# MCU.net
KiCad netlist of a schematic drawn in Altium Designer
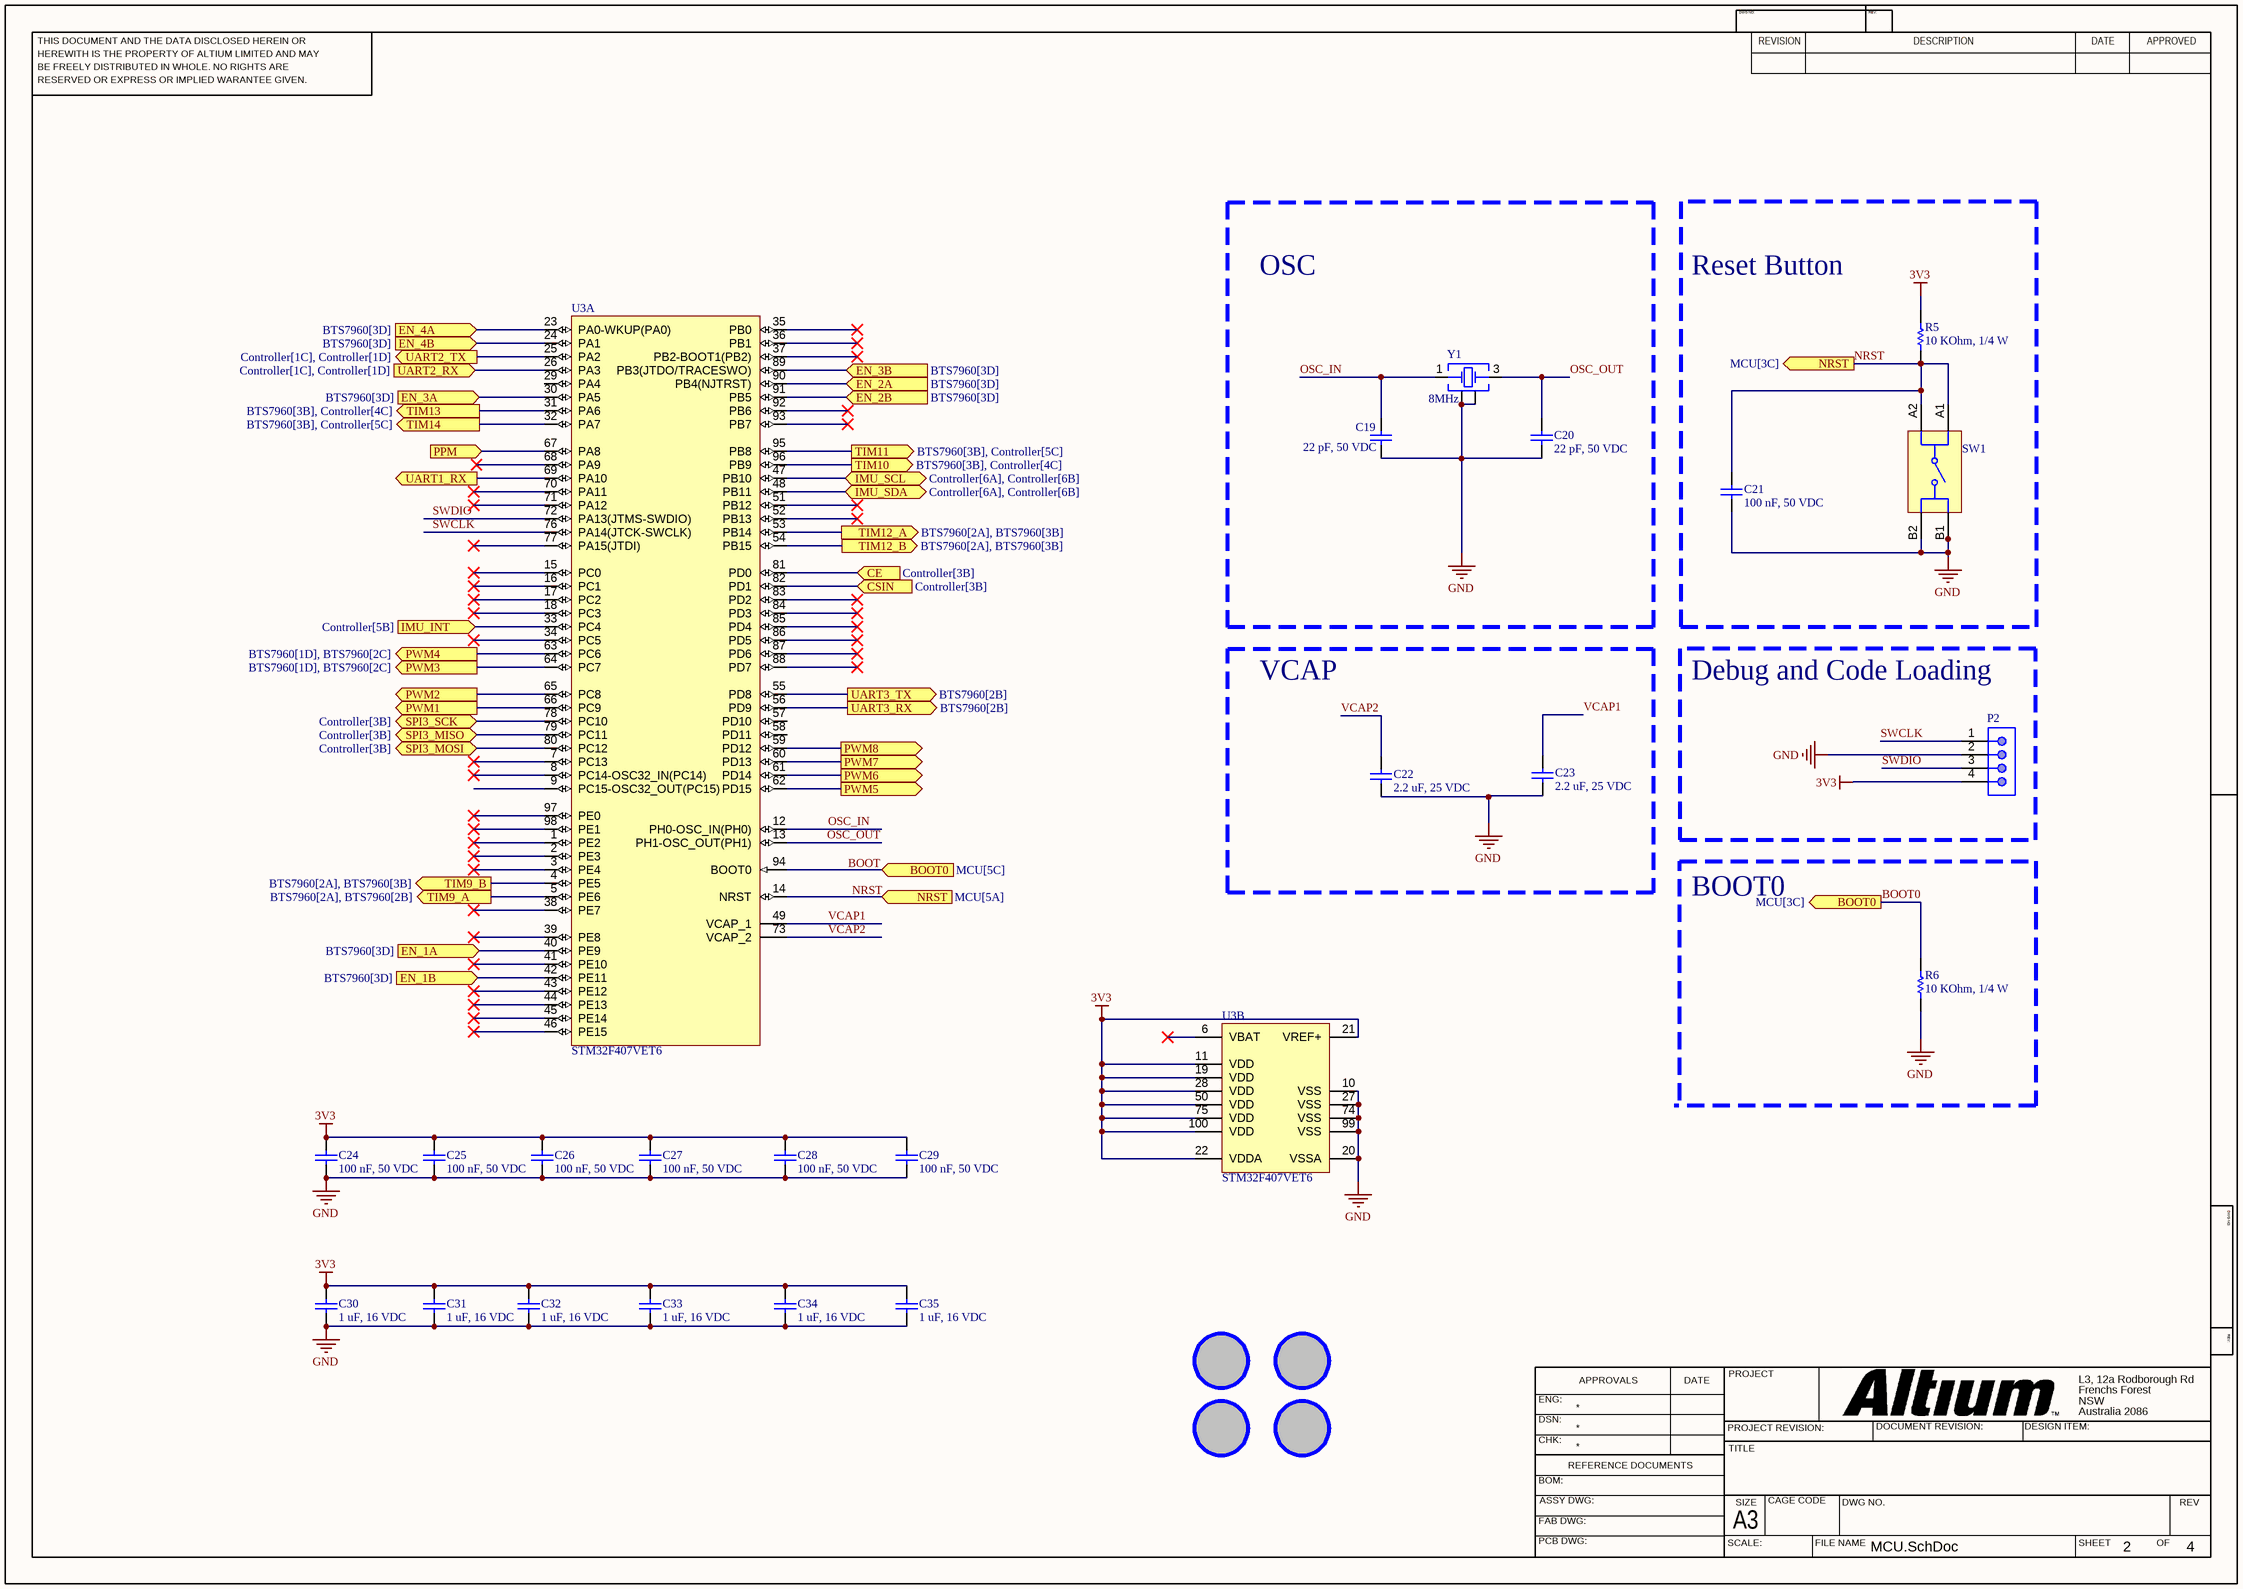
[diagram p0: MCU.SchDoc]

(export (version "E")
  (design (tool "Eeschema 10.0.6"))
  (components
    (comp (ref "C19")
      (value "22 pF, 50 VDC")
      (footprint "CAP_0603")
      (description "CAP, size 0603, 22 pF, 50 VDC")
      (fields (field (name "TOLERANCE") "+/-5%"))
      (libsource (lib "Altium_Ceramic_Cap") (part "0106032200550"))
    )
    (comp (ref "C20")
      (value "22 pF, 50 VDC")
      (footprint "CAP_0603")
      (description "CAP, size 0603, 22 pF, 50 VDC")
      (fields (field (name "TOLERANCE") "+/-5%"))
      (libsource (lib "Altium_Ceramic_Cap") (part "0106032200550"))
    )
    (comp (ref "C21")
      (value "100 nF, 50 VDC")
      (footprint "CAP_0603")
      (description "CAP, size 0603, 100 nF, 50 VDC")
      (fields (field (name "TOLERANCE") "+/-10%"))
      (libsource (lib "Altium_Ceramic_Cap") (part "0106031041050"))
    )
    (comp (ref "C22")
      (value "2.2 uF, 25 VDC")
      (footprint "CAP_0805")
      (description "CAP, size 0805, 2.2 uF, 25 VDC")
      (fields (field (name "TOLERANCE") "+/-10%"))
      (libsource (lib "Altium_Ceramic_Cap") (part "0108052251025"))
    )
    (comp (ref "C23")
      (value "2.2 uF, 25 VDC")
      (footprint "CAP_0805")
      (description "CAP, size 0805, 2.2 uF, 25 VDC")
      (fields (field (name "TOLERANCE") "+/-10%"))
      (libsource (lib "Altium_Ceramic_Cap") (part "0108052251025"))
    )
    (comp (ref "C24")
      (value "100 nF, 50 VDC")
      (footprint "CAP_0805")
      (description "CAP, size 0805, 100 nF, 50 VDC")
      (fields (field (name "TOLERANCE") "+/-5%"))
      (libsource (lib "Altium_Ceramic_Cap") (part "0108051031050"))
    )
    (comp (ref "C25")
      (value "100 nF, 50 VDC")
      (footprint "CAP_0805")
      (description "CAP, size 0805, 100 nF, 50 VDC")
      (fields (field (name "TOLERANCE") "+/-5%"))
      (libsource (lib "Altium_Ceramic_Cap") (part "0108051031050"))
    )
    (comp (ref "C26")
      (value "100 nF, 50 VDC")
      (footprint "CAP_0805")
      (description "CAP, size 0805, 100 nF, 50 VDC")
      (fields (field (name "TOLERANCE") "+/-5%"))
      (libsource (lib "Altium_Ceramic_Cap") (part "0108051031050"))
    )
    (comp (ref "C27")
      (value "100 nF, 50 VDC")
      (footprint "CAP_0805")
      (description "CAP, size 0805, 100 nF, 50 VDC")
      (fields (field (name "TOLERANCE") "+/-5%"))
      (libsource (lib "Altium_Ceramic_Cap") (part "0108051031050"))
    )
    (comp (ref "C28")
      (value "100 nF, 50 VDC")
      (footprint "CAP_0805")
      (description "CAP, size 0805, 100 nF, 50 VDC")
      (fields (field (name "TOLERANCE") "+/-5%"))
      (libsource (lib "Altium_Ceramic_Cap") (part "0108051031050"))
    )
    (comp (ref "C29")
      (value "100 nF, 50 VDC")
      (footprint "CAP_0805")
      (description "CAP, size 0805, 100 nF, 50 VDC")
      (fields (field (name "TOLERANCE") "+/-5%"))
      (libsource (lib "Altium_Ceramic_Cap") (part "0108051031050"))
    )
    (comp (ref "C30")
      (value "1 uF, 16 VDC")
      (footprint "CAP_0805")
      (description "CAP, size 0805, 1 uF, 16 VDC")
      (fields (field (name "TOLERANCE") "+/-10%"))
      (libsource (lib "Altium_Ceramic_Cap") (part "0108051051016"))
    )
    (comp (ref "C31")
      (value "1 uF, 16 VDC")
      (footprint "CAP_0805")
      (description "CAP, size 0805, 1 uF, 16 VDC")
      (fields (field (name "TOLERANCE") "+/-10%"))
      (libsource (lib "Altium_Ceramic_Cap") (part "0108051051016"))
    )
    (comp (ref "C32")
      (value "1 uF, 16 VDC")
      (footprint "CAP_0805")
      (description "CAP, size 0805, 1 uF, 16 VDC")
      (fields (field (name "TOLERANCE") "+/-10%"))
      (libsource (lib "Altium_Ceramic_Cap") (part "0108051051016"))
    )
    (comp (ref "C33")
      (value "1 uF, 16 VDC")
      (footprint "CAP_0805")
      (description "CAP, size 0805, 1 uF, 16 VDC")
      (fields (field (name "TOLERANCE") "+/-10%"))
      (libsource (lib "Altium_Ceramic_Cap") (part "0108051051016"))
    )
    (comp (ref "C34")
      (value "1 uF, 16 VDC")
      (footprint "CAP_0805")
      (description "CAP, size 0805, 1 uF, 16 VDC")
      (fields (field (name "TOLERANCE") "+/-10%"))
      (libsource (lib "Altium_Ceramic_Cap") (part "0108051051016"))
    )
    (comp (ref "C35")
      (value "1 uF, 16 VDC")
      (footprint "CAP_0805")
      (description "CAP, size 0805, 1 uF, 16 VDC")
      (fields (field (name "TOLERANCE") "+/-10%"))
      (libsource (lib "Altium_Ceramic_Cap") (part "0108051051016"))
    )
    (comp (ref "P2")
      (value "61300411121")
      (footprint "61300411121")
      (description "WR-PHD Pin Header, THT, pitch 2.54mm, Single Row, Vertical, 4p")
      (fields (field (name "MANUFACTURER") "Wurth Elektronik"))
      (libsource (lib "Altium_Header") (part "61300411121"))
    )
    (comp (ref "R5")
      (value "10 KOhm, 1/4 W")
      (footprint "resistor_0603")
      (description "RES, size 0603, 10 KOhm, 1/4 W")
      (libsource (lib "Altium_Resistor") (part "0006031031"))
    )
    (comp (ref "R6")
      (value "10 KOhm, 1/4 W")
      (footprint "resistor_0603")
      (description "RES, size 0603, 10 KOhm, 1/4 W")
      (libsource (lib "Altium_Resistor") (part "0006031031"))
    )
    (comp (ref "SW1")
      (value "430181038816")
      (footprint "WS-TASV_L4.5W4.5H3.8_430181038816")
      (description "WS-TASV SMT Tact Switch, L4.5 x W4.5 x H3.8mm, 160g, SPST-NO, 12V, 50mA")
      (fields (field (name "MANUFACTURER") "Wurth Elektronik"))
      (libsource (lib "Altium_Button") (part "430181038816"))
    )
    (comp (ref "U3")
      (value "STM32F407VET6")
      (footprint "STM-LQFP100_V")
      (fields (field (name "MANUFACTURER") "STMicroelectronics"))
      (libsource (lib "Altium Content Vault") (part "MC-ARM-STM32F40X_41X-SQ100"))
    )
    (comp (ref "Y1")
      (value "8MHz")
      (footprint "WE-XTAL_CFPX-180")
      (description "WE-XTAL Quartz Crystal, SMT, CFPX-180, 12MHz, +/-30ppm")
      (fields
        (field (name "MANUFACTURER PART NUMBER") "NX3225SA-12MHZ-STD-CSR-6")
        (field (name "MANUFACTURER") "NDK")
      )
      (libsource (lib "Altium_XTAL") (part "073525126010"))
    )
  )
  (nets
    (net (code "2") (name "/BOOT0") (class "Default")
      (node (ref "R6") (pin "2") (pinfunction "2_2") (pintype "passive"))
      (node (ref "U3") (pin "94") (pinfunction "BOOT0_94") (pintype "input"))
    )
    (net (code "3") (name "/CE") (class "Default")
      (node (ref "U3") (pin "81") (pinfunction "PD0_81") (pintype "bidirectional"))
    )
    (net (code "4") (name "/CSIN") (class "Default")
      (node (ref "U3") (pin "82") (pinfunction "PD1_82") (pintype "bidirectional"))
    )
    (net (code "5") (name "/EN_1A") (class "Default")
      (node (ref "U3") (pin "40") (pinfunction "PE9_40") (pintype "bidirectional"))
    )
    (net (code "6") (name "/EN_1B") (class "Default")
      (node (ref "U3") (pin "42") (pinfunction "PE11_42") (pintype "bidirectional"))
    )
    (net (code "7") (name "/EN_2A") (class "Default")
      (node (ref "U3") (pin "90") (pinfunction "PB4(NJTRST)_90") (pintype "bidirectional"))
    )
    (net (code "8") (name "/EN_2B") (class "Default")
      (node (ref "U3") (pin "91") (pinfunction "PB5_91") (pintype "bidirectional"))
    )
    (net (code "9") (name "/EN_3A") (class "Default")
      (node (ref "U3") (pin "30") (pinfunction "PA5_30") (pintype "bidirectional"))
    )
    (net (code "10") (name "/EN_3B") (class "Default")
      (node (ref "U3") (pin "89") (pinfunction "PB3(JTDO/TRACESWO)_89") (pintype "bidirectional"))
    )
    (net (code "11") (name "/EN_4A") (class "Default")
      (node (ref "U3") (pin "23") (pinfunction "PA0-WKUP(PA0)_23") (pintype "bidirectional"))
    )
    (net (code "12") (name "/EN_4B") (class "Default")
      (node (ref "U3") (pin "24") (pinfunction "PA1_24") (pintype "bidirectional"))
    )
    (net (code "13") (name "/IMU_INT") (class "Default")
      (node (ref "U3") (pin "33") (pinfunction "PC4_33") (pintype "bidirectional"))
    )
    (net (code "14") (name "/IMU_SCL") (class "Default")
      (node (ref "U3") (pin "47") (pinfunction "PB10_47") (pintype "bidirectional"))
    )
    (net (code "15") (name "/IMU_SDA") (class "Default")
      (node (ref "U3") (pin "48") (pinfunction "PB11_48") (pintype "bidirectional"))
    )
    (net (code "16") (name "/NRST") (class "Default")
      (node (ref "C21") (pin "1") (pinfunction "1_1") (pintype "passive"))
      (node (ref "R5") (pin "1") (pinfunction "1_1") (pintype "passive"))
      (node (ref "SW1") (pin "A1") (pinfunction "A1_A1") (pintype "passive"))
      (node (ref "SW1") (pin "A2") (pinfunction "A2_A2") (pintype "passive"))
      (node (ref "U3") (pin "14") (pinfunction "NRST_14") (pintype "bidirectional"))
    )
    (net (code "17") (name "/OSC_IN") (class "Default")
      (node (ref "C19") (pin "2") (pinfunction "2_2") (pintype "passive"))
      (node (ref "U3") (pin "12") (pinfunction "PH0-OSC_IN(PH0)_12") (pintype "bidirectional"))
      (node (ref "Y1") (pin "1") (pinfunction "Crystal_1") (pintype "passive"))
    )
    (net (code "18") (name "/OSC_OUT") (class "Default")
      (node (ref "C20") (pin "2") (pinfunction "2_2") (pintype "passive"))
      (node (ref "U3") (pin "13") (pinfunction "PH1-OSC_OUT(PH1)_13") (pintype "bidirectional"))
      (node (ref "Y1") (pin "3") (pinfunction "Crystal_3") (pintype "passive"))
    )
    (net (code "19") (name "/PPM") (class "Default")
      (node (ref "U3") (pin "67") (pinfunction "PA8_67") (pintype "bidirectional"))
    )
    (net (code "20") (name "/PWM1") (class "Default")
      (node (ref "U3") (pin "66") (pinfunction "PC9_66") (pintype "bidirectional"))
    )
    (net (code "21") (name "/PWM2") (class "Default")
      (node (ref "U3") (pin "65") (pinfunction "PC8_65") (pintype "bidirectional"))
    )
    (net (code "22") (name "/PWM3") (class "Default")
      (node (ref "U3") (pin "64") (pinfunction "PC7_64") (pintype "bidirectional"))
    )
    (net (code "23") (name "/PWM4") (class "Default")
      (node (ref "U3") (pin "63") (pinfunction "PC6_63") (pintype "bidirectional"))
    )
    (net (code "24") (name "/PWM5") (class "Default")
      (node (ref "U3") (pin "62") (pinfunction "PD15_62") (pintype "bidirectional"))
    )
    (net (code "25") (name "/PWM6") (class "Default")
      (node (ref "U3") (pin "61") (pinfunction "PD14_61") (pintype "bidirectional"))
    )
    (net (code "26") (name "/PWM7") (class "Default")
      (node (ref "U3") (pin "60") (pinfunction "PD13_60") (pintype "bidirectional"))
    )
    (net (code "27") (name "/PWM8") (class "Default")
      (node (ref "U3") (pin "59") (pinfunction "PD12_59") (pintype "bidirectional"))
    )
    (net (code "28") (name "/SPI3_MISO") (class "Default")
      (node (ref "U3") (pin "79") (pinfunction "PC11_79") (pintype "bidirectional"))
    )
    (net (code "29") (name "/SPI3_MOSI") (class "Default")
      (node (ref "U3") (pin "80") (pinfunction "PC12_80") (pintype "bidirectional"))
    )
    (net (code "30") (name "/SPI3_SCK") (class "Default")
      (node (ref "U3") (pin "78") (pinfunction "PC10_78") (pintype "bidirectional"))
    )
    (net (code "31") (name "/SWCLK") (class "Default")
      (node (ref "P2") (pin "1") (pinfunction "1_1") (pintype "passive"))
      (node (ref "U3") (pin "76") (pinfunction "PA14(JTCK-SWCLK)_76") (pintype "bidirectional"))
    )
    (net (code "32") (name "/SWDIO") (class "Default")
      (node (ref "P2") (pin "3") (pinfunction "3_3") (pintype "passive"))
      (node (ref "U3") (pin "72") (pinfunction "PA13(JTMS-SWDIO)_72") (pintype "bidirectional"))
    )
    (net (code "33") (name "/TIM9_A") (class "Default")
      (node (ref "U3") (pin "5") (pinfunction "PE6_5") (pintype "bidirectional"))
    )
    (net (code "34") (name "/TIM9_B") (class "Default")
      (node (ref "U3") (pin "4") (pinfunction "PE5_4") (pintype "bidirectional"))
    )
    (net (code "35") (name "/TIM10") (class "Default")
      (node (ref "U3") (pin "96") (pinfunction "PB9_96") (pintype "bidirectional"))
    )
    (net (code "36") (name "/TIM11") (class "Default")
      (node (ref "U3") (pin "95") (pinfunction "PB8_95") (pintype "bidirectional"))
    )
    (net (code "37") (name "/TIM12_A") (class "Default")
      (node (ref "U3") (pin "53") (pinfunction "PB14_53") (pintype "bidirectional"))
    )
    (net (code "38") (name "/TIM12_B") (class "Default")
      (node (ref "U3") (pin "54") (pinfunction "PB15_54") (pintype "bidirectional"))
    )
    (net (code "39") (name "/TIM13") (class "Default")
      (node (ref "U3") (pin "31") (pinfunction "PA6_31") (pintype "bidirectional"))
    )
    (net (code "40") (name "/TIM14") (class "Default")
      (node (ref "U3") (pin "32") (pinfunction "PA7_32") (pintype "bidirectional"))
    )
    (net (code "41") (name "/UART1_RX") (class "Default")
      (node (ref "U3") (pin "69") (pinfunction "PA10_69") (pintype "bidirectional"))
    )
    (net (code "42") (name "/UART2_RX") (class "Default")
      (node (ref "U3") (pin "26") (pinfunction "PA3_26") (pintype "bidirectional"))
    )
    (net (code "43") (name "/UART2_TX") (class "Default")
      (node (ref "U3") (pin "25") (pinfunction "PA2_25") (pintype "bidirectional"))
    )
    (net (code "44") (name "/UART3_RX") (class "Default")
      (node (ref "U3") (pin "56") (pinfunction "PD9_56") (pintype "bidirectional"))
    )
    (net (code "45") (name "/UART3_TX") (class "Default")
      (node (ref "U3") (pin "55") (pinfunction "PD8_55") (pintype "bidirectional"))
    )
    (net (code "46") (name "/VCAP1") (class "Default")
      (node (ref "C23") (pin "2") (pinfunction "2_2") (pintype "passive"))
      (node (ref "U3") (pin "49") (pinfunction "VCAP_1_49") (pintype "power_in"))
    )
    (net (code "47") (name "/VCAP2") (class "Default")
      (node (ref "C22") (pin "2") (pinfunction "2_2") (pintype "passive"))
      (node (ref "U3") (pin "73") (pinfunction "VCAP_2_73") (pintype "power_in"))
    )
    (net (code "48") (name "3V3") (class "Default")
      (node (ref "C24") (pin "2") (pinfunction "2_2") (pintype "passive"))
      (node (ref "C25") (pin "2") (pinfunction "2_2") (pintype "passive"))
      (node (ref "C26") (pin "2") (pinfunction "2_2") (pintype "passive"))
      (node (ref "C27") (pin "2") (pinfunction "2_2") (pintype "passive"))
      (node (ref "C28") (pin "2") (pinfunction "2_2") (pintype "passive"))
      (node (ref "C29") (pin "2") (pinfunction "2_2") (pintype "passive"))
      (node (ref "C30") (pin "2") (pinfunction "2_2") (pintype "passive"))
      (node (ref "C31") (pin "2") (pinfunction "2_2") (pintype "passive"))
      (node (ref "C32") (pin "2") (pinfunction "2_2") (pintype "passive"))
      (node (ref "C33") (pin "2") (pinfunction "2_2") (pintype "passive"))
      (node (ref "C34") (pin "2") (pinfunction "2_2") (pintype "passive"))
      (node (ref "C35") (pin "2") (pinfunction "2_2") (pintype "passive"))
      (node (ref "P2") (pin "4") (pinfunction "4_4") (pintype "passive"))
      (node (ref "R5") (pin "2") (pinfunction "2_2") (pintype "passive"))
      (node (ref "U3") (pin "100") (pinfunction "VDD_100") (pintype "power_in"))
      (node (ref "U3") (pin "11") (pinfunction "VDD_11") (pintype "power_in"))
      (node (ref "U3") (pin "19") (pinfunction "VDD_19") (pintype "power_in"))
      (node (ref "U3") (pin "21") (pinfunction "VREF+_21") (pintype "power_in"))
      (node (ref "U3") (pin "22") (pinfunction "VDDA_22") (pintype "power_in"))
      (node (ref "U3") (pin "28") (pinfunction "VDD_28") (pintype "power_in"))
      (node (ref "U3") (pin "50") (pinfunction "VDD_50") (pintype "power_in"))
      (node (ref "U3") (pin "75") (pinfunction "VDD_75") (pintype "power_in"))
    )
    (net (code "49") (name "GND") (class "Default")
      (node (ref "C19") (pin "1") (pinfunction "1_1") (pintype "passive"))
      (node (ref "C20") (pin "1") (pinfunction "1_1") (pintype "passive"))
      (node (ref "C21") (pin "2") (pinfunction "2_2") (pintype "passive"))
      (node (ref "C22") (pin "1") (pinfunction "1_1") (pintype "passive"))
      (node (ref "C23") (pin "1") (pinfunction "1_1") (pintype "passive"))
      (node (ref "C24") (pin "1") (pinfunction "1_1") (pintype "passive"))
      (node (ref "C25") (pin "1") (pinfunction "1_1") (pintype "passive"))
      (node (ref "C26") (pin "1") (pinfunction "1_1") (pintype "passive"))
      (node (ref "C27") (pin "1") (pinfunction "1_1") (pintype "passive"))
      (node (ref "C28") (pin "1") (pinfunction "1_1") (pintype "passive"))
      (node (ref "C29") (pin "1") (pinfunction "1_1") (pintype "passive"))
      (node (ref "C30") (pin "1") (pinfunction "1_1") (pintype "passive"))
      (node (ref "C31") (pin "1") (pinfunction "1_1") (pintype "passive"))
      (node (ref "C32") (pin "1") (pinfunction "1_1") (pintype "passive"))
      (node (ref "C33") (pin "1") (pinfunction "1_1") (pintype "passive"))
      (node (ref "C34") (pin "1") (pinfunction "1_1") (pintype "passive"))
      (node (ref "C35") (pin "1") (pinfunction "1_1") (pintype "passive"))
      (node (ref "P2") (pin "2") (pinfunction "2_2") (pintype "passive"))
      (node (ref "R6") (pin "1") (pinfunction "1_1") (pintype "passive"))
      (node (ref "SW1") (pin "B1") (pinfunction "B1_B1") (pintype "passive"))
      (node (ref "SW1") (pin "B2") (pinfunction "B2_B2") (pintype "passive"))
      (node (ref "U3") (pin "10") (pinfunction "VSS_10") (pintype "power_in"))
      (node (ref "U3") (pin "20") (pinfunction "VSSA_20") (pintype "power_in"))
      (node (ref "U3") (pin "27") (pinfunction "VSS_27") (pintype "power_in"))
      (node (ref "U3") (pin "74") (pinfunction "VSS_74") (pintype "power_in"))
      (node (ref "U3") (pin "99") (pinfunction "VSS_99") (pintype "power_in"))
      (node (ref "Y1") (pin "2") (pinfunction "GND_2") (pintype "passive"))
      (node (ref "Y1") (pin "4") (pinfunction "GND_4") (pintype "passive"))
    )
    (net (code "54") (name "unconnected-(U3A-PA4-Pad29)") (class "Default")
      (node (ref "U3") (pin "29") (pinfunction "PA4_29") (pintype "bidirectional"))
    )
    (net (code "55") (name "unconnected-(U3A-PA9-Pad68)") (class "Default")
      (node (ref "U3") (pin "68") (pinfunction "PA9_68") (pintype "bidirectional+no_connect"))
    )
    (net (code "56") (name "unconnected-(U3A-PA11-Pad70)") (class "Default")
      (node (ref "U3") (pin "70") (pinfunction "PA11_70") (pintype "bidirectional+no_connect"))
    )
    (net (code "57") (name "unconnected-(U3A-PA12-Pad71)") (class "Default")
      (node (ref "U3") (pin "71") (pinfunction "PA12_71") (pintype "bidirectional+no_connect"))
    )
    (net (code "58") (name "unconnected-(U3A-PA15(JTDI)-Pad77)") (class "Default")
      (node (ref "U3") (pin "77") (pinfunction "PA15(JTDI)_77") (pintype "bidirectional+no_connect"))
    )
    (net (code "59") (name "unconnected-(U3A-PB0-Pad35)") (class "Default")
      (node (ref "U3") (pin "35") (pinfunction "PB0_35") (pintype "bidirectional+no_connect"))
    )
    (net (code "60") (name "unconnected-(U3A-PB1-Pad36)") (class "Default")
      (node (ref "U3") (pin "36") (pinfunction "PB1_36") (pintype "bidirectional+no_connect"))
    )
    (net (code "61") (name "unconnected-(U3A-PB2-BOOT1(PB2)-Pad37)") (class "Default")
      (node (ref "U3") (pin "37") (pinfunction "PB2-BOOT1(PB2)_37") (pintype "bidirectional+no_connect"))
    )
    (net (code "62") (name "unconnected-(U3A-PB6-Pad92)") (class "Default")
      (node (ref "U3") (pin "92") (pinfunction "PB6_92") (pintype "bidirectional+no_connect"))
    )
    (net (code "63") (name "unconnected-(U3A-PB7-Pad93)") (class "Default")
      (node (ref "U3") (pin "93") (pinfunction "PB7_93") (pintype "bidirectional+no_connect"))
    )
    (net (code "64") (name "unconnected-(U3A-PB12-Pad51)") (class "Default")
      (node (ref "U3") (pin "51") (pinfunction "PB12_51") (pintype "bidirectional+no_connect"))
    )
    (net (code "65") (name "unconnected-(U3A-PB13-Pad52)") (class "Default")
      (node (ref "U3") (pin "52") (pinfunction "PB13_52") (pintype "bidirectional+no_connect"))
    )
    (net (code "66") (name "unconnected-(U3A-PC0-Pad15)") (class "Default")
      (node (ref "U3") (pin "15") (pinfunction "PC0_15") (pintype "bidirectional+no_connect"))
    )
    (net (code "67") (name "unconnected-(U3A-PC1-Pad16)") (class "Default")
      (node (ref "U3") (pin "16") (pinfunction "PC1_16") (pintype "bidirectional+no_connect"))
    )
    (net (code "68") (name "unconnected-(U3A-PC2-Pad17)") (class "Default")
      (node (ref "U3") (pin "17") (pinfunction "PC2_17") (pintype "bidirectional+no_connect"))
    )
    (net (code "69") (name "unconnected-(U3A-PC3-Pad18)") (class "Default")
      (node (ref "U3") (pin "18") (pinfunction "PC3_18") (pintype "bidirectional+no_connect"))
    )
    (net (code "70") (name "unconnected-(U3A-PC5-Pad34)") (class "Default")
      (node (ref "U3") (pin "34") (pinfunction "PC5_34") (pintype "bidirectional+no_connect"))
    )
    (net (code "71") (name "unconnected-(U3A-PC13-Pad7)") (class "Default")
      (node (ref "U3") (pin "7") (pinfunction "PC13_7") (pintype "bidirectional+no_connect"))
    )
    (net (code "72") (name "unconnected-(U3A-PC14-OSC32_IN(PC14)-Pad8)") (class "Default")
      (node (ref "U3") (pin "8") (pinfunction "PC14-OSC32_IN(PC14)_8") (pintype "bidirectional+no_connect"))
    )
    (net (code "73") (name "unconnected-(U3A-PC15-OSC32_OUT(PC15)-Pad9)") (class "Default")
      (node (ref "U3") (pin "9") (pinfunction "PC15-OSC32_OUT(PC15)_9") (pintype "bidirectional"))
    )
    (net (code "74") (name "unconnected-(U3A-PD2-Pad83)") (class "Default")
      (node (ref "U3") (pin "83") (pinfunction "PD2_83") (pintype "bidirectional+no_connect"))
    )
    (net (code "75") (name "unconnected-(U3A-PD3-Pad84)") (class "Default")
      (node (ref "U3") (pin "84") (pinfunction "PD3_84") (pintype "bidirectional+no_connect"))
    )
    (net (code "76") (name "unconnected-(U3A-PD4-Pad85)") (class "Default")
      (node (ref "U3") (pin "85") (pinfunction "PD4_85") (pintype "bidirectional+no_connect"))
    )
    (net (code "77") (name "unconnected-(U3A-PD5-Pad86)") (class "Default")
      (node (ref "U3") (pin "86") (pinfunction "PD5_86") (pintype "bidirectional+no_connect"))
    )
    (net (code "78") (name "unconnected-(U3A-PD6-Pad87)") (class "Default")
      (node (ref "U3") (pin "87") (pinfunction "PD6_87") (pintype "bidirectional+no_connect"))
    )
    (net (code "79") (name "unconnected-(U3A-PD7-Pad88)") (class "Default")
      (node (ref "U3") (pin "88") (pinfunction "PD7_88") (pintype "bidirectional+no_connect"))
    )
    (net (code "80") (name "unconnected-(U3A-PD10-Pad57)") (class "Default")
      (node (ref "U3") (pin "57") (pinfunction "PD10_57") (pintype "bidirectional"))
    )
    (net (code "81") (name "unconnected-(U3A-PD11-Pad58)") (class "Default")
      (node (ref "U3") (pin "58") (pinfunction "PD11_58") (pintype "bidirectional"))
    )
    (net (code "82") (name "unconnected-(U3A-PE0-Pad97)") (class "Default")
      (node (ref "U3") (pin "97") (pinfunction "PE0_97") (pintype "bidirectional+no_connect"))
    )
    (net (code "83") (name "unconnected-(U3A-PE1-Pad98)") (class "Default")
      (node (ref "U3") (pin "98") (pinfunction "PE1_98") (pintype "bidirectional+no_connect"))
    )
    (net (code "84") (name "unconnected-(U3A-PE2-Pad1)") (class "Default")
      (node (ref "U3") (pin "1") (pinfunction "PE2_1") (pintype "bidirectional+no_connect"))
    )
    (net (code "85") (name "unconnected-(U3A-PE3-Pad2)") (class "Default")
      (node (ref "U3") (pin "2") (pinfunction "PE3_2") (pintype "bidirectional+no_connect"))
    )
    (net (code "86") (name "unconnected-(U3A-PE4-Pad3)") (class "Default")
      (node (ref "U3") (pin "3") (pinfunction "PE4_3") (pintype "bidirectional+no_connect"))
    )
    (net (code "87") (name "unconnected-(U3A-PE7-Pad38)") (class "Default")
      (node (ref "U3") (pin "38") (pinfunction "PE7_38") (pintype "bidirectional+no_connect"))
    )
    (net (code "88") (name "unconnected-(U3A-PE8-Pad39)") (class "Default")
      (node (ref "U3") (pin "39") (pinfunction "PE8_39") (pintype "bidirectional+no_connect"))
    )
    (net (code "89") (name "unconnected-(U3A-PE10-Pad41)") (class "Default")
      (node (ref "U3") (pin "41") (pinfunction "PE10_41") (pintype "bidirectional+no_connect"))
    )
    (net (code "90") (name "unconnected-(U3A-PE12-Pad43)") (class "Default")
      (node (ref "U3") (pin "43") (pinfunction "PE12_43") (pintype "bidirectional+no_connect"))
    )
    (net (code "91") (name "unconnected-(U3A-PE13-Pad44)") (class "Default")
      (node (ref "U3") (pin "44") (pinfunction "PE13_44") (pintype "bidirectional+no_connect"))
    )
    (net (code "92") (name "unconnected-(U3A-PE14-Pad45)") (class "Default")
      (node (ref "U3") (pin "45") (pinfunction "PE14_45") (pintype "bidirectional+no_connect"))
    )
    (net (code "93") (name "unconnected-(U3A-PE15-Pad46)") (class "Default")
      (node (ref "U3") (pin "46") (pinfunction "PE15_46") (pintype "bidirectional+no_connect"))
    )
    (net (code "94") (name "unconnected-(U3B-VBAT-Pad6)") (class "Default")
      (node (ref "U3") (pin "6") (pinfunction "VBAT_6") (pintype "power_in+no_connect"))
    )
  )
)
